# usb.net
KiCad netlist of a schematic drawn in Altium Designer
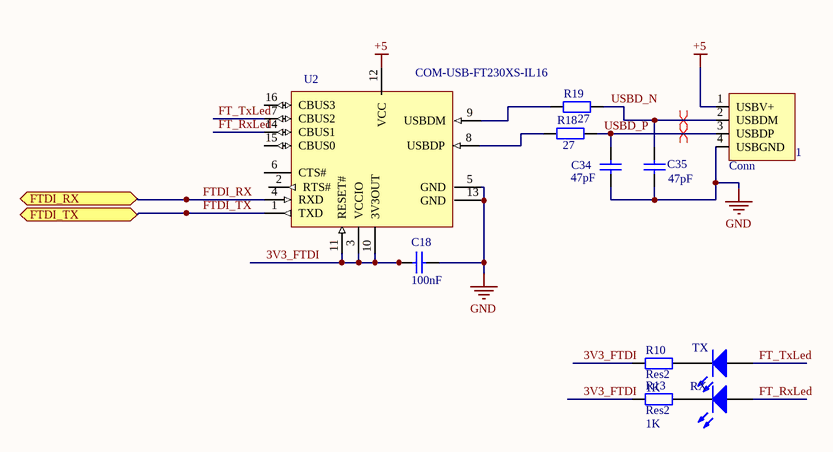
[diagram p0: usb.SchDoc]

(export (version "E")
  (design (tool "Eeschema 10.0.6"))
  (components
    (comp (ref "C18")
      (value "100nF")
      (footprint "CAPC2012M")
      (description "Capacitor")
      (fields (field (name "Comment") "Cap") (field (name "PUBLISHER") "Altium Limited"))
      (libsource (lib "Miscellaneous Devices") (part "Cap"))
    )
    (comp (ref "C34")
      (value "47pF")
      (footprint "CAPC1005M")
      (description "Capacitor")
      (fields (field (name "Comment") "Cap") (field (name "PUBLISHER") "Altium Limited"))
      (libsource (lib "Miscellaneous Devices") (part "Cap"))
    )
    (comp (ref "C35")
      (value "47pF")
      (footprint "CAPC1005M")
      (description "Capacitor")
      (fields (field (name "Comment") "Cap") (field (name "PUBLISHER") "Altium Limited"))
      (libsource (lib "Miscellaneous Devices") (part "Cap"))
    )
    (comp (ref "CN1")
      (value "Conn")
      (footprint "USB2.5-2H4D")
      (description "USBB-1J")
      (fields (field (name "AC MAGNITUDE") "1"))
      (libsource (lib "Schlib1") (part "USBB-1J"))
    )
    (comp (ref "R10")
      (value "Res2")
      (footprint "RESC2012M")
      (description "Resistor")
      (fields (field (name "ALTIUM_VALUE") "1K") (field (name "PUBLISHER") "Altium Limited"))
      (libsource (lib "Miscellaneous Devices") (part "Res2"))
    )
    (comp (ref "R13")
      (value "Res2")
      (footprint "RESC2012M")
      (description "Resistor")
      (fields (field (name "ALTIUM_VALUE") "1K") (field (name "PUBLISHER") "Altium Limited"))
      (libsource (lib "Miscellaneous Devices") (part "Res2"))
    )
    (comp (ref "R18")
      (value "27")
      (footprint "RESC2012M")
      (description "Resistor")
      (fields (field (name "Comment") "Res") (field (name "PUBLISHER") "Altium Limited"))
      (libsource (lib "Miscellaneous Devices") (part "Res2"))
    )
    (comp (ref "R19")
      (value "27")
      (footprint "RESC2012M")
      (description "Resistor")
      (fields (field (name "Comment") "Res") (field (name "PUBLISHER") "Altium Limited"))
      (libsource (lib "Miscellaneous Devices") (part "Res2"))
    )
    (comp (ref "RX")
      (value "led")
      (footprint "RESC2012M")
      (description "chip led")
      (libsource (lib "Schlib1") (part "chip led"))
    )
    (comp (ref "TX")
      (value "led")
      (footprint "RESC2012M")
      (description "chip led")
      (libsource (lib "Schlib1") (part "chip led"))
    )
    (comp (ref "U2")
      (value "COM-USB-FT230XS-IL16")
      (footprint "SSOP-16_M")
      (description "FTDI FT230XS")
      (libsource (lib "ftdi") (part "COM-USB-FT230XS-IL16"))
    )
  )
  (nets
    (net (code "1") (name "+5") (class "Default")
      (node (ref "CN1") (pin "1") (pinfunction "USBV+_1") (pintype "power_in"))
      (node (ref "U2") (pin "12") (pinfunction "VCC_12") (pintype "power_in"))
    )
    (net (code "2") (name "/3V3_FTDI") (class "Default")
      (node (ref "C18") (pin "1") (pinfunction "1_1") (pintype "passive"))
      (node (ref "R10") (pin "1") (pinfunction "1_1") (pintype "passive"))
      (node (ref "R13") (pin "1") (pinfunction "1_1") (pintype "passive"))
      (node (ref "U2") (pin "10") (pinfunction "3V3OUT_10") (pintype "power_in"))
      (node (ref "U2") (pin "11") (pinfunction "RESET#_11") (pintype "input"))
      (node (ref "U2") (pin "3") (pinfunction "VCCIO_3") (pintype "power_in"))
    )
    (net (code "3") (name "/FTDI_RX") (class "Default")
      (node (ref "U2") (pin "4") (pinfunction "RXD_4") (pintype "input"))
    )
    (net (code "4") (name "/FTDI_TX") (class "Default")
      (node (ref "U2") (pin "1") (pinfunction "TXD_1") (pintype "output"))
    )
    (net (code "5") (name "/FT_RxLed") (class "Default")
      (node (ref "RX") (pin "1") (pinfunction "A_1") (pintype "passive"))
      (node (ref "U2") (pin "14") (pinfunction "CBUS1_14") (pintype "bidirectional"))
    )
    (net (code "6") (name "/FT_TxLed") (class "Default")
      (node (ref "TX") (pin "1") (pinfunction "A_1") (pintype "passive"))
      (node (ref "U2") (pin "7") (pinfunction "CBUS2_7") (pintype "bidirectional"))
    )
    (net (code "7") (name "/USBD_N") (class "Default")
      (node (ref "C35") (pin "2") (pinfunction "2_2") (pintype "passive"))
      (node (ref "CN1") (pin "2") (pinfunction "USBDM_2") (pintype "passive"))
      (node (ref "R19") (pin "2") (pinfunction "2_2") (pintype "passive"))
    )
    (net (code "8") (name "/USBD_P") (class "Default")
      (node (ref "C34") (pin "2") (pinfunction "2_2") (pintype "passive"))
      (node (ref "CN1") (pin "3") (pinfunction "USBDP_3") (pintype "passive"))
      (node (ref "R18") (pin "2") (pinfunction "2_2") (pintype "passive"))
    )
    (net (code "9") (name "GND") (class "Default")
      (node (ref "C18") (pin "2") (pinfunction "2_2") (pintype "passive"))
      (node (ref "C34") (pin "1") (pinfunction "1_1") (pintype "passive"))
      (node (ref "C35") (pin "1") (pinfunction "1_1") (pintype "passive"))
      (node (ref "CN1") (pin "4") (pinfunction "USBGND_4") (pintype "power_in"))
      (node (ref "U2") (pin "13") (pinfunction "GND_13") (pintype "power_in"))
      (node (ref "U2") (pin "5") (pinfunction "GND_5") (pintype "power_in"))
    )
    (net (code "10") (name "Net-(RX-K)") (class "Default")
      (node (ref "R13") (pin "2") (pinfunction "2_2") (pintype "passive"))
      (node (ref "RX") (pin "2") (pinfunction "K_2") (pintype "passive"))
    )
    (net (code "11") (name "Net-(TX-K)") (class "Default")
      (node (ref "R10") (pin "2") (pinfunction "2_2") (pintype "passive"))
      (node (ref "TX") (pin "2") (pinfunction "K_2") (pintype "passive"))
    )
    (net (code "12") (name "Net-(U2-USBDM)") (class "Default")
      (node (ref "R19") (pin "1") (pinfunction "1_1") (pintype "passive"))
      (node (ref "U2") (pin "9") (pinfunction "USBDM_9") (pintype "input"))
    )
    (net (code "13") (name "Net-(U2-USBDP)") (class "Default")
      (node (ref "R18") (pin "1") (pinfunction "1_1") (pintype "passive"))
      (node (ref "U2") (pin "8") (pinfunction "USBDP_8") (pintype "input"))
    )
    (net (code "14") (name "unconnected-(U2-CBUS0-Pad15)") (class "Default")
      (node (ref "U2") (pin "15") (pinfunction "CBUS0_15") (pintype "bidirectional"))
    )
    (net (code "15") (name "unconnected-(U2-CBUS3-Pad16)") (class "Default")
      (node (ref "U2") (pin "16") (pinfunction "CBUS3_16") (pintype "bidirectional"))
    )
    (net (code "16") (name "unconnected-(U2-CTS#-Pad6)") (class "Default")
      (node (ref "U2") (pin "6") (pinfunction "CTS#_6") (pintype "passive"))
    )
    (net (code "17") (name "unconnected-(U2-RTS#-Pad2)") (class "Default")
      (node (ref "U2") (pin "2") (pinfunction "RTS#_2") (pintype "output"))
    )
  )
)
